# SCH_NFC-CARD_2026-05-23.net
KiCad netlist of a schematic drawn in EasyEDA
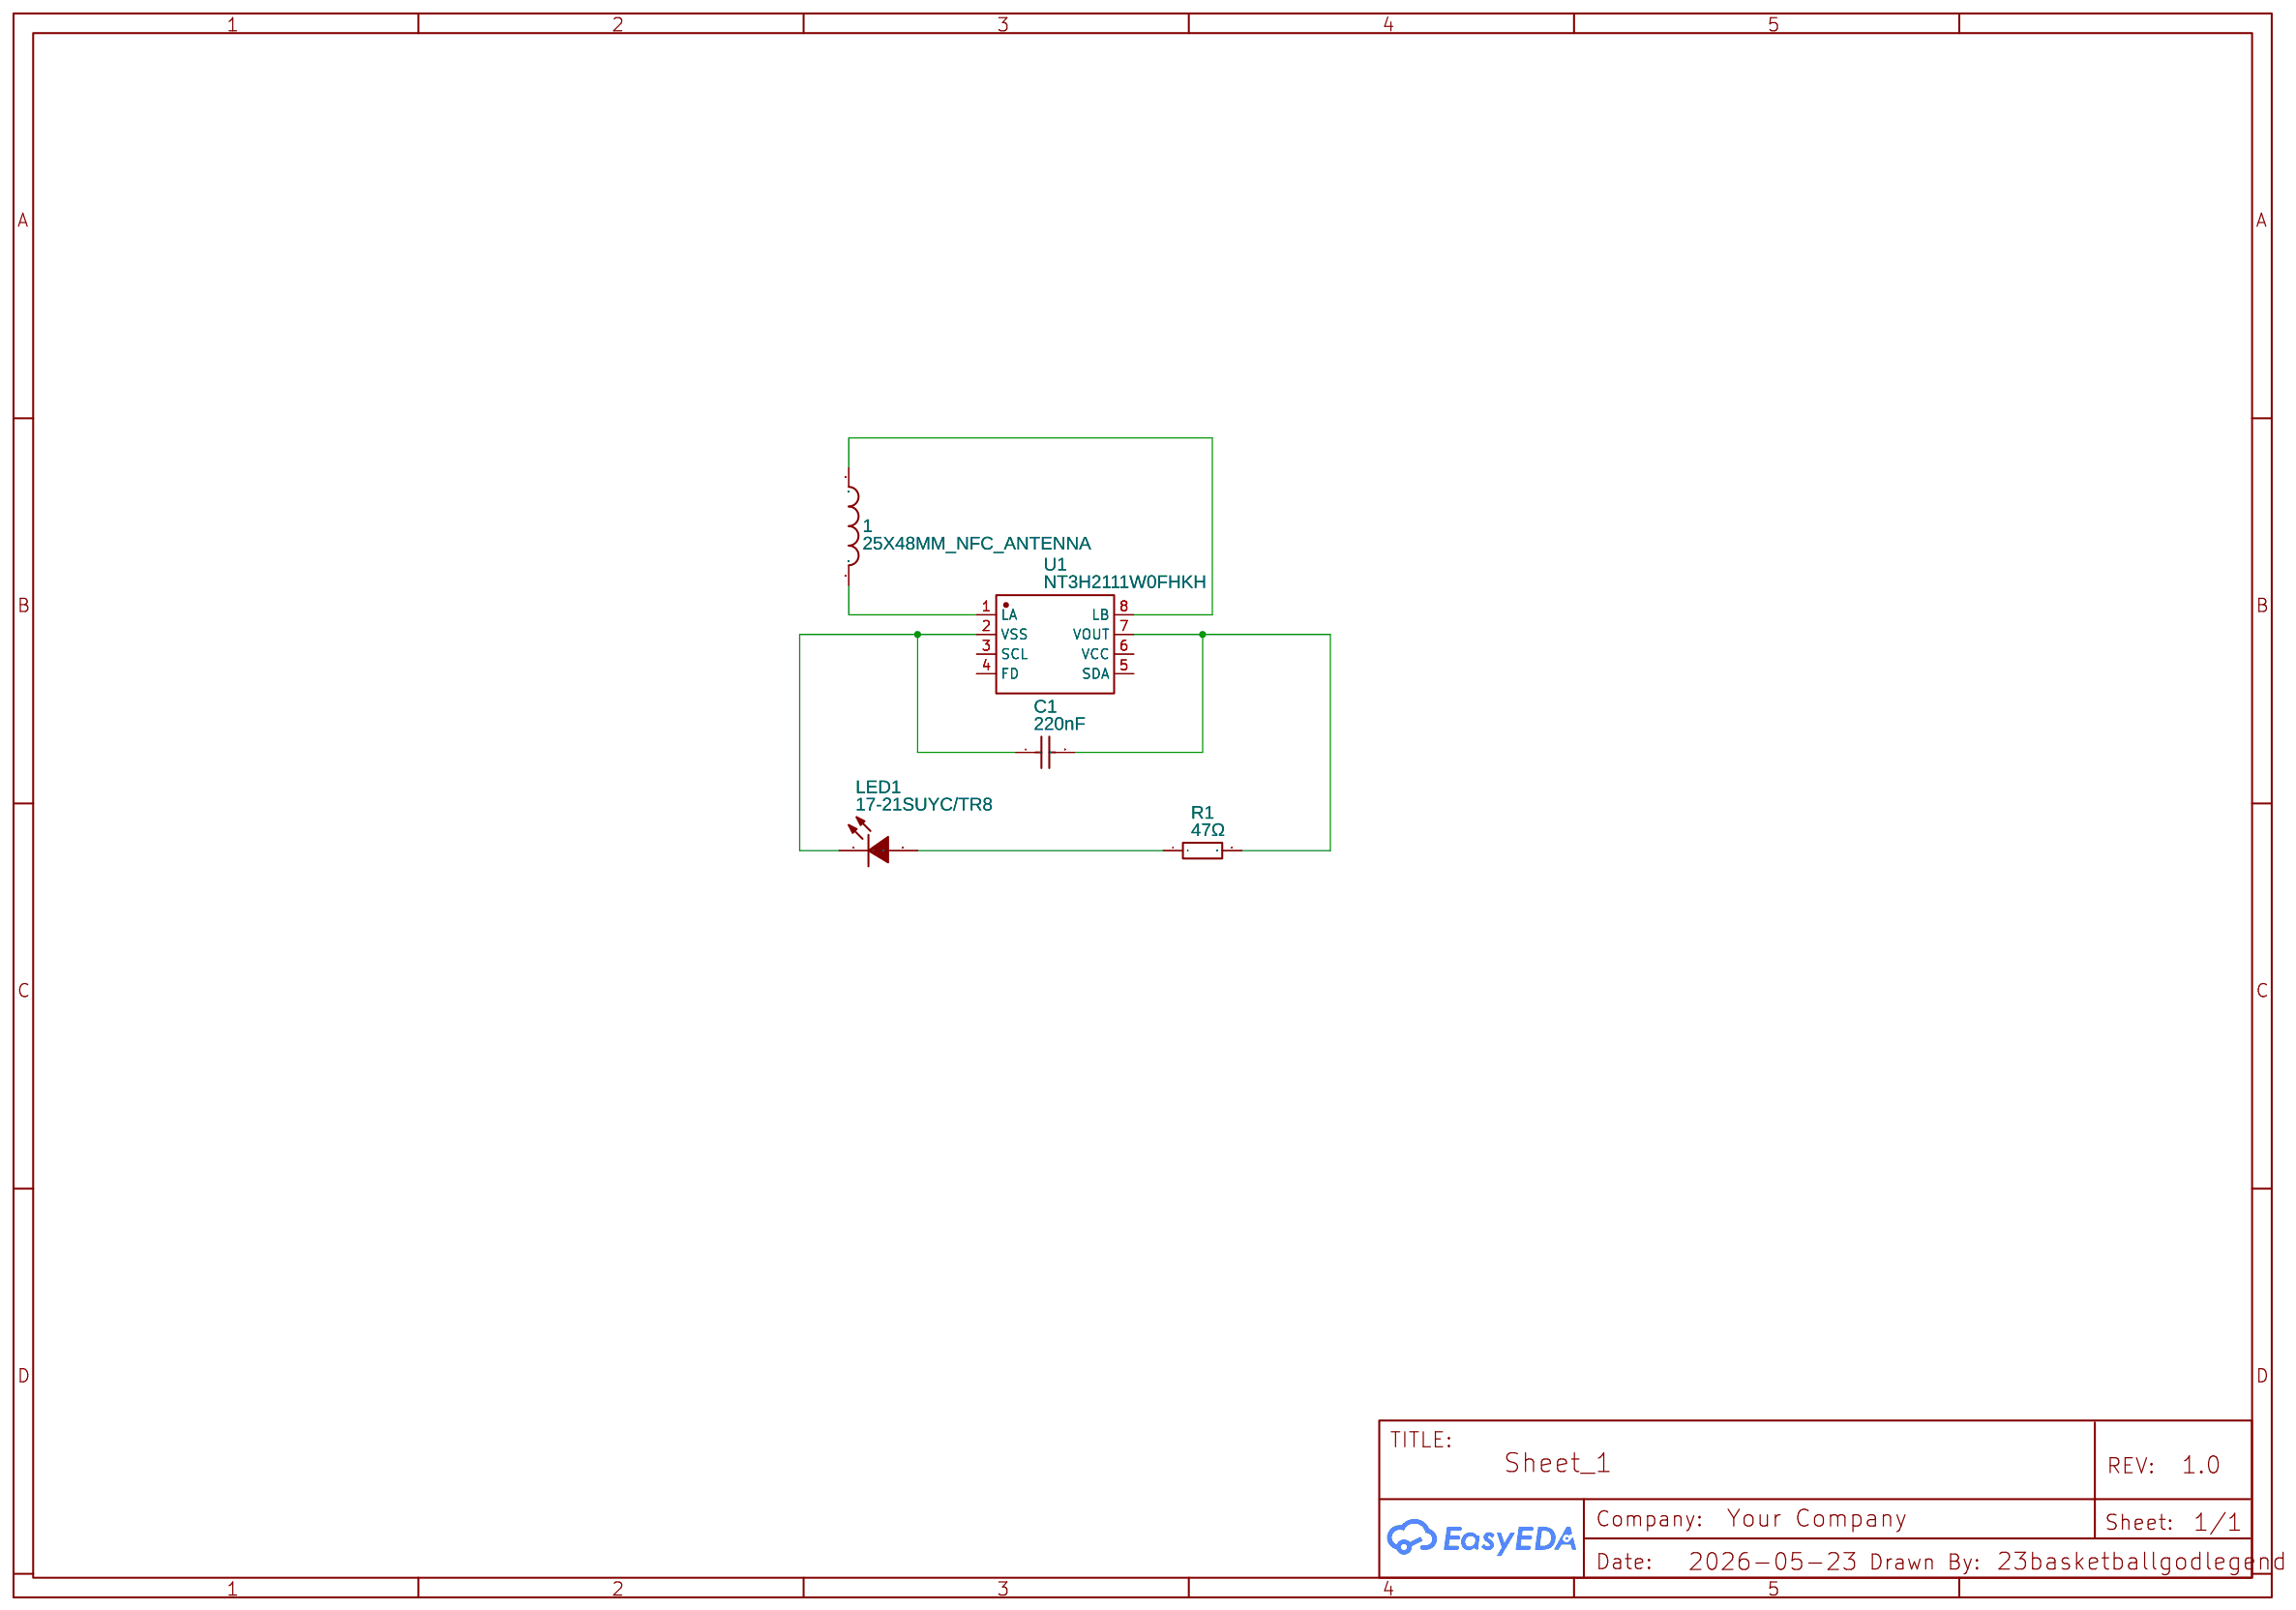
[diagram p0: schematic sheet]

(export (version "E")
  (design (tool "Eeschema 10.0.6"))
  (components
    (comp (ref "1") (value "25X48MM_NFC_ANTENNA") (libsource (lib "") (part "25X48MM_NFC_ANTENNA")))
    (comp (ref "C1")
      (value "220nF")
      (fields
        (field (name "Manufacturer Part") "CL10B224KA8NNNC")
        (field (name "Manufacturer") "SAMSUNG(三星)")
      )
      (libsource (lib "") (part "CL10B224KA8NNNC"))
    )
    (comp (ref "LED1")
      (value "17-21SUYC/TR8")
      (fields (field (name "Manufacturer Part") "KT-0805黄灯") (field (name "Manufacturer") "KENTO"))
      (libsource (lib "") (part "17-21SUYC/TR8"))
    )
    (comp (ref "R1")
      (value "47Ω")
      (fields
        (field (name "Manufacturer Part") "0603WAF470JT5E")
        (field (name "Manufacturer") "UNI-ROYAL(厚声)")
      )
      (libsource (lib "") (part "0603WAF470JT5E"))
    )
    (comp (ref "U1")
      (value "NT3H2111W0FHKH")
      (fields (field (name "Manufacturer") "NXP(恩智浦)"))
      (libsource (lib "") (part "NT3H2111W0FHKH"))
    )
  )
  (nets
    (net (code "1") (name "Net-(LED1-+)") (class "Default")
      (node (ref "LED1") (pin "1") (pinfunction "+_1") (pintype "unspecified"))
      (node (ref "R1") (pin "1") (pinfunction "1_1") (pintype "input"))
    )
    (net (code "2") (name "Net-(LED1--)") (class "Default")
      (node (ref "C1") (pin "1") (pinfunction "1_1") (pintype "input"))
      (node (ref "LED1") (pin "2") (pinfunction "-_2") (pintype "unspecified"))
      (node (ref "U1") (pin "2") (pinfunction "VSS_2") (pintype "unspecified"))
    )
    (net (code "3") (name "Net-(U1-LA)") (class "Default")
      (node (ref "1") (pin "P$2") (pinfunction "P$2_P$2") (pintype "bidirectional"))
      (node (ref "U1") (pin "1") (pinfunction "LA_1") (pintype "unspecified"))
    )
    (net (code "4") (name "Net-(U1-LB)") (class "Default")
      (node (ref "1") (pin "P$1") (pinfunction "P$1_P$1") (pintype "bidirectional"))
      (node (ref "U1") (pin "8") (pinfunction "LB_8") (pintype "unspecified"))
    )
    (net (code "5") (name "Net-(U1-VOUT)") (class "Default")
      (node (ref "C1") (pin "2") (pinfunction "2_2") (pintype "input"))
      (node (ref "R1") (pin "2") (pinfunction "2_2") (pintype "input"))
      (node (ref "U1") (pin "7") (pinfunction "VOUT_7") (pintype "unspecified"))
    )
    (net (code "6") (name "unconnected-(U1-FD-Pad4)") (class "Default")
      (node (ref "U1") (pin "4") (pinfunction "FD_4") (pintype "unspecified"))
    )
    (net (code "7") (name "unconnected-(U1-SCL-Pad3)") (class "Default")
      (node (ref "U1") (pin "3") (pinfunction "SCL_3") (pintype "unspecified"))
    )
    (net (code "8") (name "unconnected-(U1-SDA-Pad5)") (class "Default")
      (node (ref "U1") (pin "5") (pinfunction "SDA_5") (pintype "unspecified"))
    )
    (net (code "9") (name "unconnected-(U1-VCC-Pad6)") (class "Default")
      (node (ref "U1") (pin "6") (pinfunction "VCC_6") (pintype "unspecified"))
    )
  )
)
